# qorvo_885071-A_eval.net
KiCad netlist of a schematic drawn in EAGLE
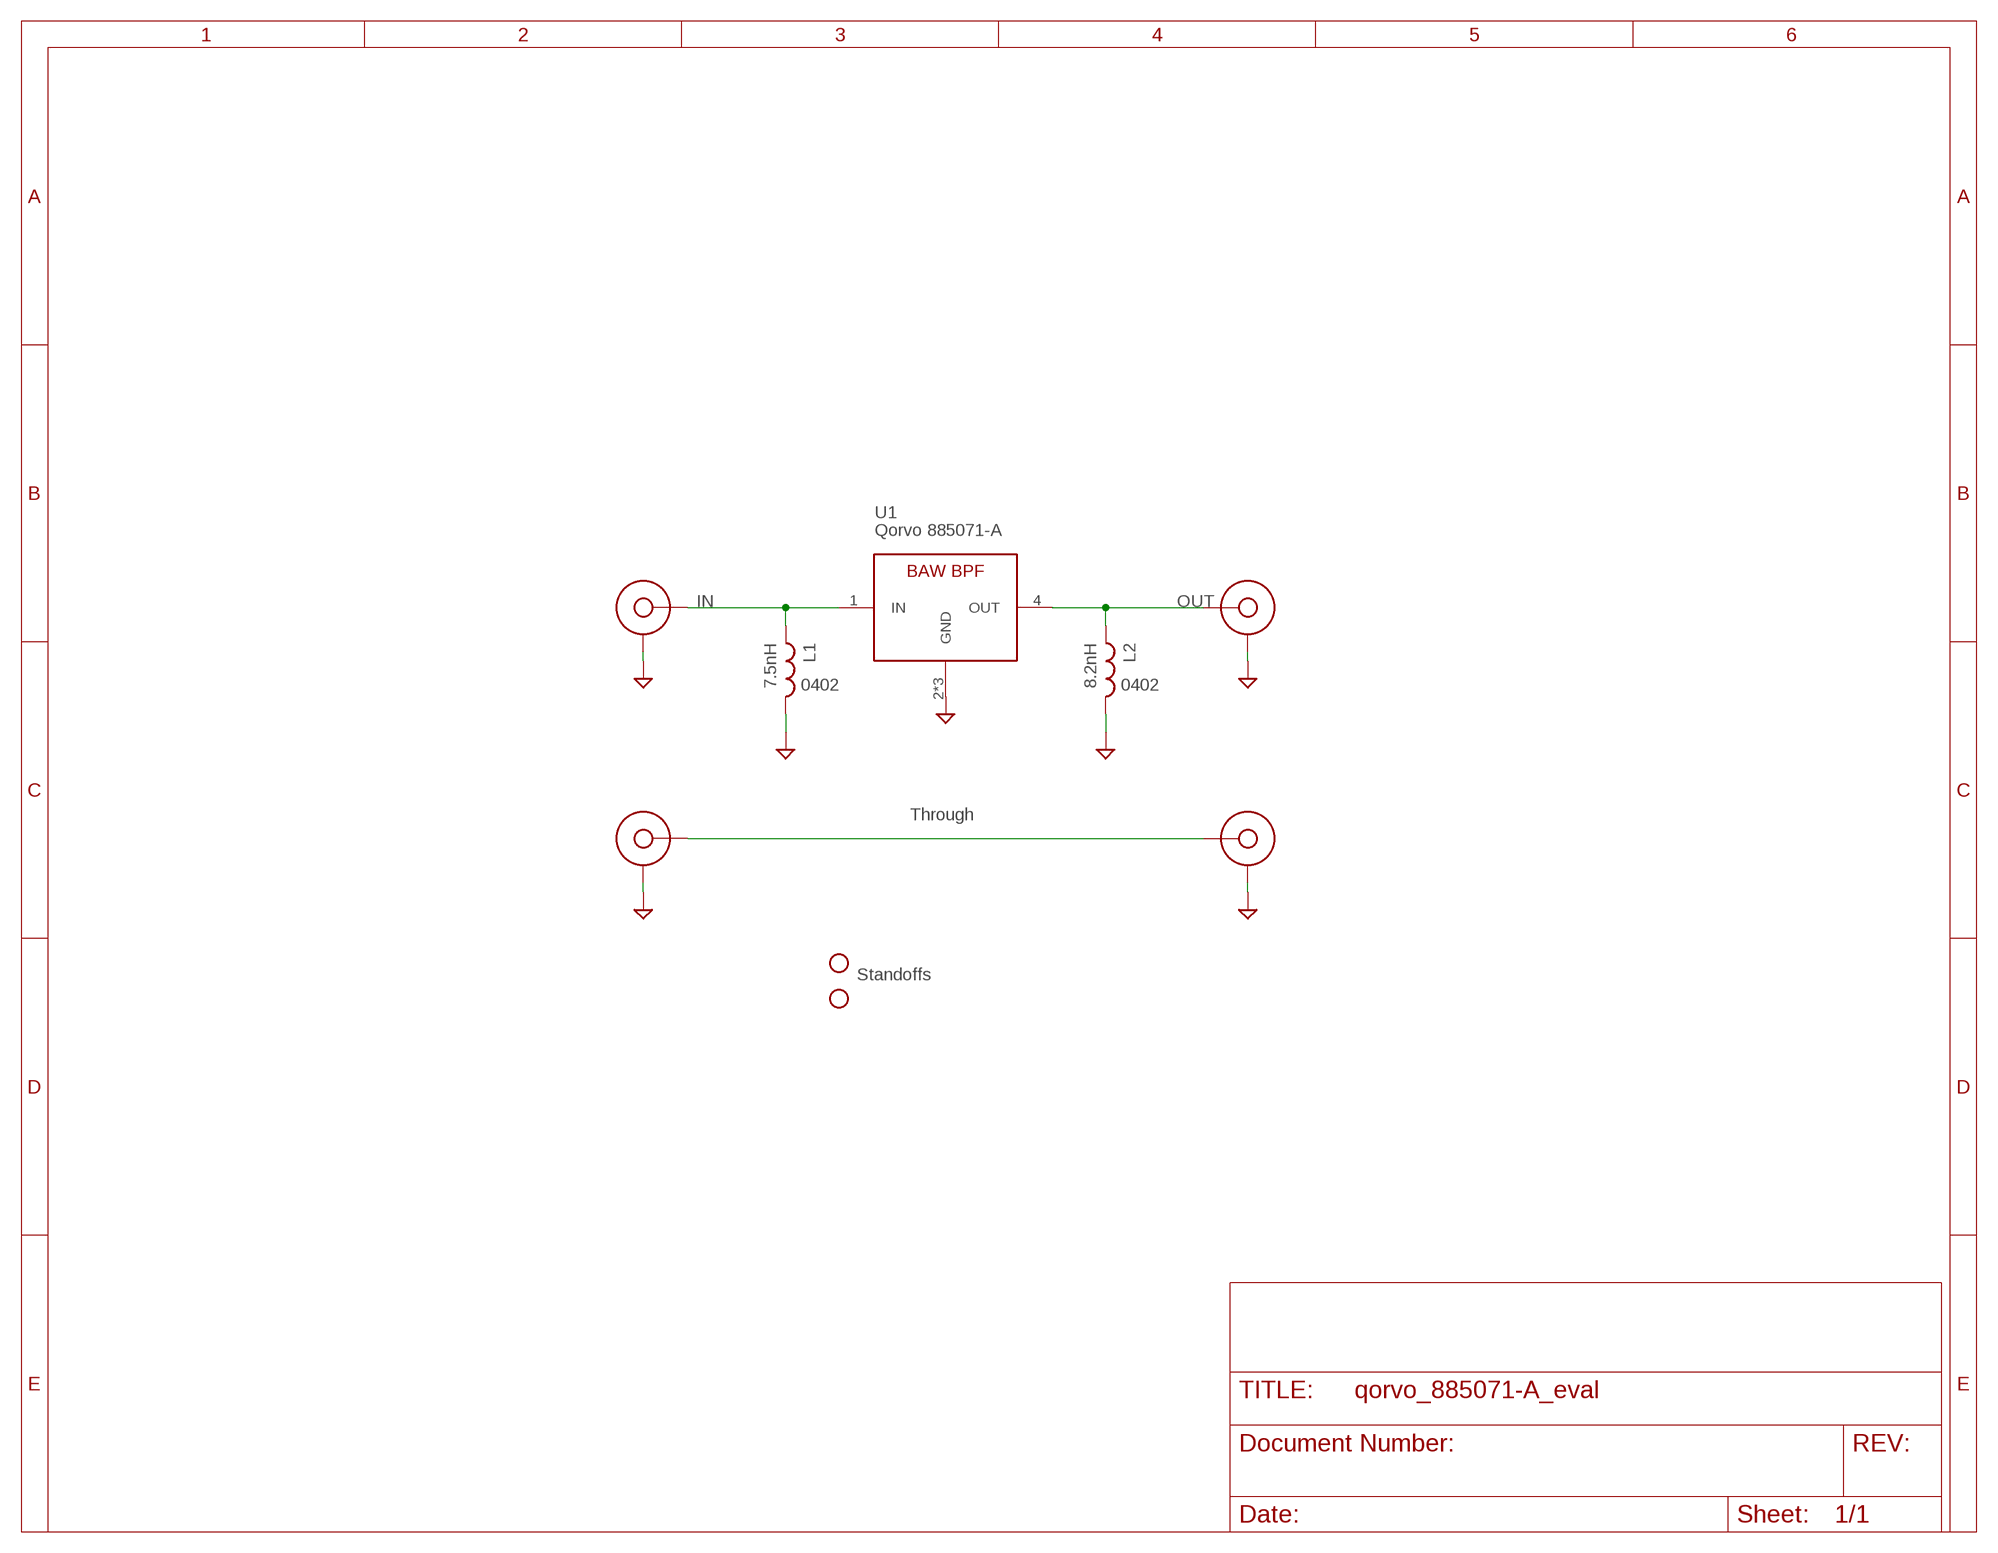
[diagram p0: schematic, sheet 1]

(export (version "E")
  (design (tool "Eeschema 10.0.6"))
  (components
    (comp (ref "CF1")
      (value "SMA-CINCH-END-FIRE")
      (footprint "eagle-import:SMAJ716-ND")
      (libsource (lib "eagle-import") (part "SMA-CINCH-END-FIRE"))
    )
    (comp (ref "CF2")
      (value "SMA-CINCH-END-FIRE")
      (footprint "eagle-import:SMAJ716-ND")
      (libsource (lib "eagle-import") (part "SMA-CINCH-END-FIRE"))
    )
    (comp (ref "CF3")
      (value "SMA-CINCH-END-FIRE")
      (footprint "eagle-import:SMAJ716-ND")
      (libsource (lib "eagle-import") (part "SMA-CINCH-END-FIRE"))
    )
    (comp (ref "CF4")
      (value "SMA-CINCH-END-FIRE")
      (footprint "eagle-import:SMAJ716-ND")
      (libsource (lib "eagle-import") (part "SMA-CINCH-END-FIRE"))
    )
    (comp (ref "H1")
      (value "STAND-OFFTIGHT")
      (footprint "eagle-import:STAND-OFF-TIGHT")
      (libsource (lib "eagle-import") (part "STAND-OFFTIGHT"))
    )
    (comp (ref "H2")
      (value "STAND-OFFTIGHT")
      (footprint "eagle-import:STAND-OFF-TIGHT")
      (libsource (lib "eagle-import") (part "STAND-OFFTIGHT"))
    )
    (comp (ref "L1")
      (value "7.5nH")
      (footprint "eagle-import:.0402-B-NOSILK")
      (libsource (lib "eagle-import") (part "L-US0402-B-NOSILK"))
    )
    (comp (ref "L2")
      (value "8.2nH")
      (footprint "eagle-import:.0402-B-NOSILK")
      (libsource (lib "eagle-import") (part "L-US0402-B-NOSILK"))
    )
    (comp (ref "U1")
      (value "885071-A")
      (footprint "eagle-import:FIL_B39162B9417K610")
      (libsource (lib "eagle-import") (part "885071-A"))
    )
  )
  (nets
    (net (code "1") (name "/IN") (class "Default")
      (node (ref "CF1") (pin "P$3") (pinfunction "CENTERCONDUCTOR_P$3") (pintype "bidirectional"))
      (node (ref "L1") (pin "1") (pinfunction "1_1") (pintype "passive"))
      (node (ref "U1") (pin "1") (pinfunction "IN_1") (pintype "passive"))
    )
    (net (code "2") (name "/OUT") (class "Default")
      (node (ref "CF3") (pin "P$3") (pinfunction "CENTERCONDUCTOR_P$3") (pintype "bidirectional"))
      (node (ref "L2") (pin "1") (pinfunction "1_1") (pintype "passive"))
      (node (ref "U1") (pin "4") (pinfunction "OUT_4") (pintype "passive"))
    )
    (net (code "3") (name "GND") (class "Default")
      (node (ref "CF1") (pin "GND1") (pinfunction "GND_GND1") (pintype "power_in"))
      (node (ref "CF1") (pin "GND2") (pinfunction "GND_GND2") (pintype "power_in"))
      (node (ref "CF1") (pin "GND3") (pinfunction "GND_GND3") (pintype "power_in"))
      (node (ref "CF1") (pin "GND4") (pinfunction "GND_GND4") (pintype "power_in"))
      (node (ref "CF2") (pin "GND1") (pinfunction "GND_GND1") (pintype "power_in"))
      (node (ref "CF2") (pin "GND2") (pinfunction "GND_GND2") (pintype "power_in"))
      (node (ref "CF2") (pin "GND3") (pinfunction "GND_GND3") (pintype "power_in"))
      (node (ref "CF2") (pin "GND4") (pinfunction "GND_GND4") (pintype "power_in"))
      (node (ref "CF3") (pin "GND1") (pinfunction "GND_GND1") (pintype "power_in"))
      (node (ref "CF3") (pin "GND2") (pinfunction "GND_GND2") (pintype "power_in"))
      (node (ref "CF3") (pin "GND3") (pinfunction "GND_GND3") (pintype "power_in"))
      (node (ref "CF3") (pin "GND4") (pinfunction "GND_GND4") (pintype "power_in"))
      (node (ref "CF4") (pin "GND1") (pinfunction "GND_GND1") (pintype "power_in"))
      (node (ref "CF4") (pin "GND2") (pinfunction "GND_GND2") (pintype "power_in"))
      (node (ref "CF4") (pin "GND3") (pinfunction "GND_GND3") (pintype "power_in"))
      (node (ref "CF4") (pin "GND4") (pinfunction "GND_GND4") (pintype "power_in"))
      (node (ref "L1") (pin "2") (pinfunction "2_2") (pintype "passive"))
      (node (ref "L2") (pin "2") (pinfunction "2_2") (pintype "passive"))
      (node (ref "U1") (pin "2") (pinfunction "GND_2") (pintype "power_in"))
      (node (ref "U1") (pin "3") (pinfunction "GND_3") (pintype "power_in"))
      (node (ref "U1") (pin "5") (pinfunction "GND_5") (pintype "power_in"))
    )
    (net (code "4") (name "Net-(CF2-CENTERCONDUCTOR)") (class "Default")
      (node (ref "CF2") (pin "P$3") (pinfunction "CENTERCONDUCTOR_P$3") (pintype "bidirectional"))
      (node (ref "CF4") (pin "P$3") (pinfunction "CENTERCONDUCTOR_P$3") (pintype "bidirectional"))
    )
  )
)
